# 3x8ButV1_3_6.net
KiCad netlist of a schematic drawn in EAGLE
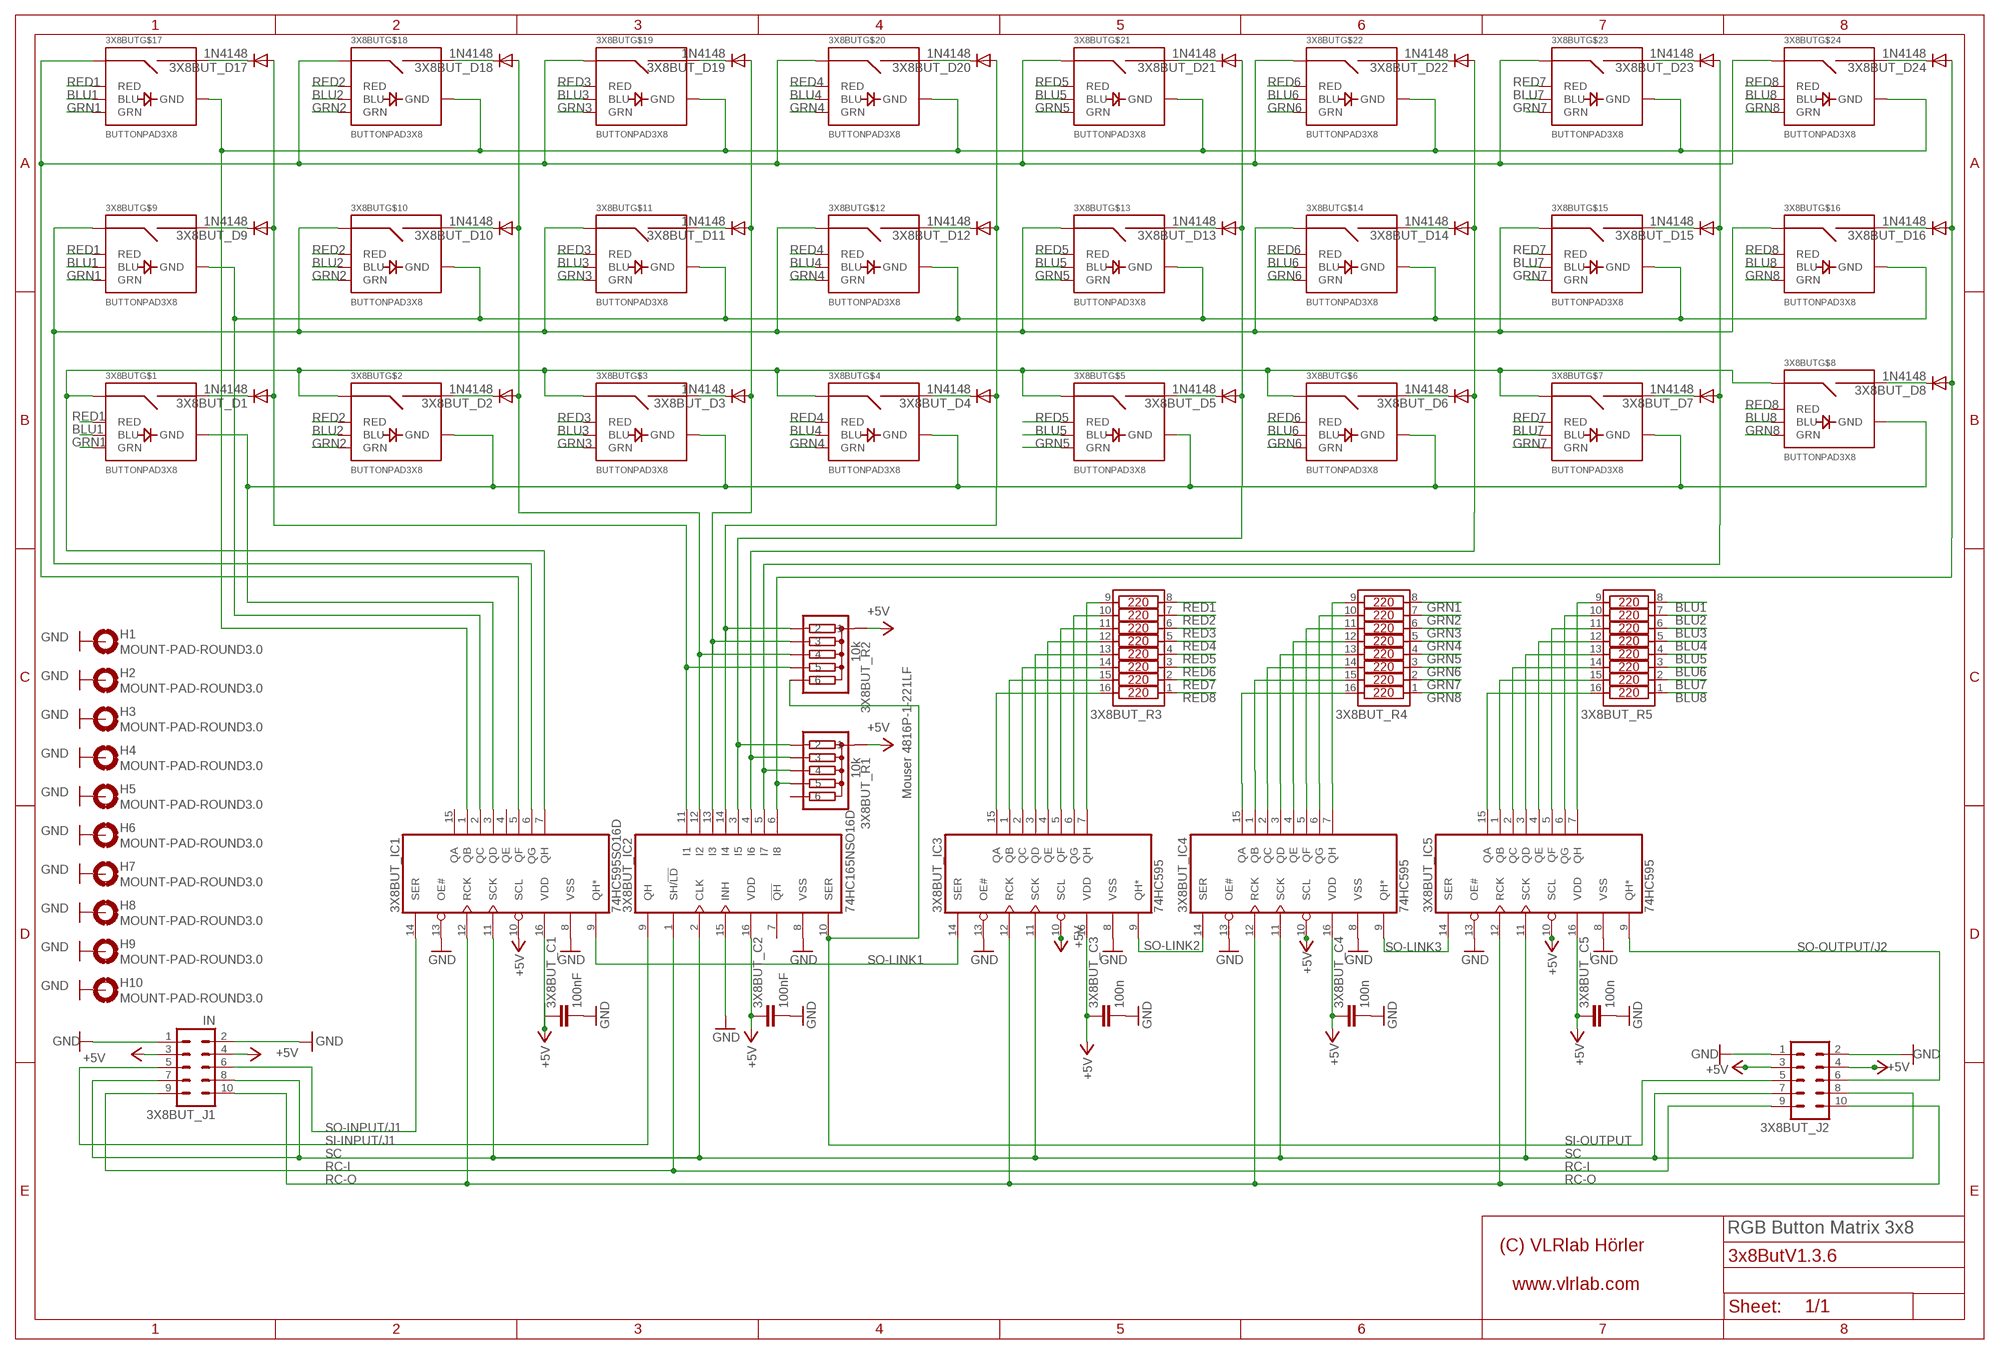
[diagram p0: schematic, sheet 1]

(export (version "E")
  (design (tool "Eeschema 10.0.6"))
  (components
    (comp (ref "3X8BUT")
      (value "BUTTONPAD3X8")
      (footprint "eagle-import:BUTTONPAD3X8")
      (libsource (lib "eagle-import") (part "BUTTONPAD3X8"))
    )
    (comp (ref "3X8BUT_C1")
      (value "100nF")
      (footprint "eagle-import:C025-030X050")
      (libsource (lib "eagle-import") (part "C-EU025-030X050"))
    )
    (comp (ref "3X8BUT_C2")
      (value "100nF")
      (footprint "eagle-import:C025-030X050")
      (libsource (lib "eagle-import") (part "C-EU025-030X050"))
    )
    (comp (ref "3X8BUT_C3")
      (value "100n")
      (footprint "eagle-import:C025-030X050")
      (libsource (lib "eagle-import") (part "C-EU025-030X050"))
    )
    (comp (ref "3X8BUT_C4")
      (value "100n")
      (footprint "eagle-import:C025-030X050")
      (libsource (lib "eagle-import") (part "C-EU025-030X050"))
    )
    (comp (ref "3X8BUT_C5")
      (value "100n")
      (footprint "eagle-import:C025-030X050")
      (libsource (lib "eagle-import") (part "C-EU025-030X050"))
    )
    (comp (ref "3X8BUT_D1")
      (value "1N4148")
      (footprint "eagle-import:DO35-7")
      (libsource (lib "eagle-import") (part "1N4148"))
    )
    (comp (ref "3X8BUT_D2")
      (value "1N4148")
      (footprint "eagle-import:DO35-7")
      (libsource (lib "eagle-import") (part "1N4148"))
    )
    (comp (ref "3X8BUT_D3")
      (value "1N4148")
      (footprint "eagle-import:DO35-7")
      (libsource (lib "eagle-import") (part "1N4148"))
    )
    (comp (ref "3X8BUT_D4")
      (value "1N4148")
      (footprint "eagle-import:DO35-7")
      (libsource (lib "eagle-import") (part "1N4148"))
    )
    (comp (ref "3X8BUT_D5")
      (value "1N4148")
      (footprint "eagle-import:DO35-7")
      (libsource (lib "eagle-import") (part "1N4148"))
    )
    (comp (ref "3X8BUT_D6")
      (value "1N4148")
      (footprint "eagle-import:DO35-7")
      (libsource (lib "eagle-import") (part "1N4148"))
    )
    (comp (ref "3X8BUT_D7")
      (value "1N4148")
      (footprint "eagle-import:DO35-7")
      (libsource (lib "eagle-import") (part "1N4148"))
    )
    (comp (ref "3X8BUT_D8")
      (value "1N4148")
      (footprint "eagle-import:DO35-7")
      (libsource (lib "eagle-import") (part "1N4148"))
    )
    (comp (ref "3X8BUT_D9")
      (value "1N4148")
      (footprint "eagle-import:DO35-7")
      (libsource (lib "eagle-import") (part "1N4148"))
    )
    (comp (ref "3X8BUT_D10")
      (value "1N4148")
      (footprint "eagle-import:DO35-7")
      (libsource (lib "eagle-import") (part "1N4148"))
    )
    (comp (ref "3X8BUT_D11")
      (value "1N4148")
      (footprint "eagle-import:DO35-7")
      (libsource (lib "eagle-import") (part "1N4148"))
    )
    (comp (ref "3X8BUT_D12")
      (value "1N4148")
      (footprint "eagle-import:DO35-7")
      (libsource (lib "eagle-import") (part "1N4148"))
    )
    (comp (ref "3X8BUT_D13")
      (value "1N4148")
      (footprint "eagle-import:DO35-7")
      (libsource (lib "eagle-import") (part "1N4148"))
    )
    (comp (ref "3X8BUT_D14")
      (value "1N4148")
      (footprint "eagle-import:DO35-7")
      (libsource (lib "eagle-import") (part "1N4148"))
    )
    (comp (ref "3X8BUT_D15")
      (value "1N4148")
      (footprint "eagle-import:DO35-7")
      (libsource (lib "eagle-import") (part "1N4148"))
    )
    (comp (ref "3X8BUT_D16")
      (value "1N4148")
      (footprint "eagle-import:DO35-7")
      (libsource (lib "eagle-import") (part "1N4148"))
    )
    (comp (ref "3X8BUT_D17")
      (value "1N4148")
      (footprint "eagle-import:DO35-7")
      (libsource (lib "eagle-import") (part "1N4148"))
    )
    (comp (ref "3X8BUT_D18")
      (value "1N4148")
      (footprint "eagle-import:DO35-7")
      (libsource (lib "eagle-import") (part "1N4148"))
    )
    (comp (ref "3X8BUT_D19")
      (value "1N4148")
      (footprint "eagle-import:DO35-7")
      (libsource (lib "eagle-import") (part "1N4148"))
    )
    (comp (ref "3X8BUT_D20")
      (value "1N4148")
      (footprint "eagle-import:DO35-7")
      (libsource (lib "eagle-import") (part "1N4148"))
    )
    (comp (ref "3X8BUT_D21")
      (value "1N4148")
      (footprint "eagle-import:DO35-7")
      (libsource (lib "eagle-import") (part "1N4148"))
    )
    (comp (ref "3X8BUT_D22")
      (value "1N4148")
      (footprint "eagle-import:DO35-7")
      (libsource (lib "eagle-import") (part "1N4148"))
    )
    (comp (ref "3X8BUT_D23")
      (value "1N4148")
      (footprint "eagle-import:DO35-7")
      (libsource (lib "eagle-import") (part "1N4148"))
    )
    (comp (ref "3X8BUT_D24")
      (value "1N4148")
      (footprint "eagle-import:DO35-7")
      (libsource (lib "eagle-import") (part "1N4148"))
    )
    (comp (ref "3X8BUT_IC1")
      (value "74HC595SO16D")
      (footprint "eagle-import:SO16D")
      (libsource (lib "eagle-import") (part "595-541-165-uln2803_74HC595SO16D"))
    )
    (comp (ref "3X8BUT_IC2")
      (value "74HC165NSO16D")
      (footprint "eagle-import:SO16D")
      (libsource (lib "eagle-import") (part "74HC165NSO16D"))
    )
    (comp (ref "3X8BUT_IC3")
      (value "74HC595")
      (footprint "eagle-import:SO16D")
      (libsource (lib "eagle-import") (part "595-541-165-uln2803_74HC595SO16D"))
    )
    (comp (ref "3X8BUT_IC4")
      (value "74HC595")
      (footprint "eagle-import:SO16D")
      (libsource (lib "eagle-import") (part "595-541-165-uln2803_74HC595SO16D"))
    )
    (comp (ref "3X8BUT_IC5")
      (value "74HC595")
      (footprint "eagle-import:SO16D")
      (libsource (lib "eagle-import") (part "595-541-165-uln2803_74HC595SO16D"))
    )
    (comp (ref "3X8BUT_J1")
      (value "IN")
      (footprint "eagle-import:ML10")
      (libsource (lib "eagle-import") (part "ML10"))
    )
    (comp (ref "3X8BUT_J2")
      (value "ML10")
      (footprint "eagle-import:ML10")
      (libsource (lib "eagle-import") (part "con-ml_ML10"))
    )
    (comp (ref "3X8BUT_R1")
      (value "10k")
      (footprint "eagle-import:SIL6")
      (libsource (lib "eagle-import") (part "4306R"))
    )
    (comp (ref "3X8BUT_R2")
      (value "10k")
      (footprint "eagle-import:SIL6")
      (libsource (lib "eagle-import") (part "4306R"))
    )
    (comp (ref "3X8BUT_R3")
      (value "4816P-1SOIC16W")
      (footprint "eagle-import:SOIC16W")
      (libsource (lib "eagle-import") (part "4816P-1SOIC16W"))
    )
    (comp (ref "3X8BUT_R4")
      (value "4816P-1SOIC16W")
      (footprint "eagle-import:SOIC16W")
      (libsource (lib "eagle-import") (part "4816P-1SOIC16W"))
    )
    (comp (ref "3X8BUT_R5")
      (value "4816P-1SOIC16W")
      (footprint "eagle-import:SOIC16W")
      (libsource (lib "eagle-import") (part "4816P-1SOIC16W"))
    )
    (comp (ref "H1")
      (value "MOUNT-PAD-ROUND3.0")
      (footprint "eagle-import:3,0-PAD")
      (libsource (lib "eagle-import") (part "MOUNT-PAD-ROUND3.0"))
    )
    (comp (ref "H2")
      (value "MOUNT-PAD-ROUND3.0")
      (footprint "eagle-import:3,0-PAD")
      (libsource (lib "eagle-import") (part "MOUNT-PAD-ROUND3.0"))
    )
    (comp (ref "H3")
      (value "MOUNT-PAD-ROUND3.0")
      (footprint "eagle-import:3,0-PAD")
      (libsource (lib "eagle-import") (part "MOUNT-PAD-ROUND3.0"))
    )
    (comp (ref "H4")
      (value "MOUNT-PAD-ROUND3.0")
      (footprint "eagle-import:3,0-PAD")
      (libsource (lib "eagle-import") (part "MOUNT-PAD-ROUND3.0"))
    )
    (comp (ref "H5")
      (value "MOUNT-PAD-ROUND3.0")
      (footprint "eagle-import:3,0-PAD")
      (libsource (lib "eagle-import") (part "MOUNT-PAD-ROUND3.0"))
    )
    (comp (ref "H6")
      (value "MOUNT-PAD-ROUND3.0")
      (footprint "eagle-import:3,0-PAD")
      (libsource (lib "eagle-import") (part "MOUNT-PAD-ROUND3.0"))
    )
    (comp (ref "H7")
      (value "MOUNT-PAD-ROUND3.0")
      (footprint "eagle-import:3,0-PAD")
      (libsource (lib "eagle-import") (part "MOUNT-PAD-ROUND3.0"))
    )
    (comp (ref "H8")
      (value "MOUNT-PAD-ROUND3.0")
      (footprint "eagle-import:3,0-PAD")
      (libsource (lib "eagle-import") (part "MOUNT-PAD-ROUND3.0"))
    )
    (comp (ref "H9")
      (value "MOUNT-PAD-ROUND3.0")
      (footprint "eagle-import:3,0-PAD")
      (libsource (lib "eagle-import") (part "MOUNT-PAD-ROUND3.0"))
    )
    (comp (ref "H10")
      (value "MOUNT-PAD-ROUND3.0")
      (footprint "eagle-import:3,0-PAD")
      (libsource (lib "eagle-import") (part "MOUNT-PAD-ROUND3.0"))
    )
  )
  (nets
    (net (code "1") (name "+5V") (class "Default")
      (node (ref "3X8BUT_C1") (pin "1") (pinfunction "1_1") (pintype "passive"))
      (node (ref "3X8BUT_C2") (pin "1") (pinfunction "1_1") (pintype "passive"))
      (node (ref "3X8BUT_C3") (pin "1") (pinfunction "1_1") (pintype "passive"))
      (node (ref "3X8BUT_C4") (pin "1") (pinfunction "1_1") (pintype "passive"))
      (node (ref "3X8BUT_C5") (pin "1") (pinfunction "1_1") (pintype "passive"))
      (node (ref "3X8BUT_IC1") (pin "10") (pinfunction "SCL_10") (pintype "input"))
      (node (ref "3X8BUT_IC1") (pin "16") (pinfunction "VDD_16") (pintype "power_in"))
      (node (ref "3X8BUT_IC2") (pin "16") (pinfunction "VDD_16") (pintype "power_in"))
      (node (ref "3X8BUT_IC3") (pin "10") (pinfunction "SCL_10") (pintype "input"))
      (node (ref "3X8BUT_IC3") (pin "16") (pinfunction "VDD_16") (pintype "power_in"))
      (node (ref "3X8BUT_IC4") (pin "10") (pinfunction "SCL_10") (pintype "input"))
      (node (ref "3X8BUT_IC4") (pin "16") (pinfunction "VDD_16") (pintype "power_in"))
      (node (ref "3X8BUT_IC5") (pin "10") (pinfunction "SCL_10") (pintype "input"))
      (node (ref "3X8BUT_IC5") (pin "16") (pinfunction "VDD_16") (pintype "power_in"))
      (node (ref "3X8BUT_J1") (pin "3") (pinfunction "3_3") (pintype "passive"))
      (node (ref "3X8BUT_J1") (pin "4") (pinfunction "4_4") (pintype "passive"))
      (node (ref "3X8BUT_J2") (pin "3") (pinfunction "3_3") (pintype "passive"))
      (node (ref "3X8BUT_J2") (pin "4") (pinfunction "4_4") (pintype "passive"))
      (node (ref "3X8BUT_R1") (pin "1") (pinfunction "1_1") (pintype "passive"))
      (node (ref "3X8BUT_R2") (pin "1") (pinfunction "1_1") (pintype "passive"))
    )
    (net (code "2") (name "/BLU1") (class "Default")
      (node (ref "3X8BUT") (pin "BLU1") (pinfunction "BLU_BLU1") (pintype "bidirectional"))
      (node (ref "3X8BUT") (pin "BLU17") (pinfunction "BLU_BLU17") (pintype "bidirectional"))
      (node (ref "3X8BUT") (pin "BLU9") (pinfunction "BLU_BLU9") (pintype "bidirectional"))
      (node (ref "3X8BUT_R5") (pin "8") (pinfunction "P$8_8") (pintype "passive"))
    )
    (net (code "3") (name "/BLU2") (class "Default")
      (node (ref "3X8BUT") (pin "BLU10") (pinfunction "BLU_BLU10") (pintype "bidirectional"))
      (node (ref "3X8BUT") (pin "BLU18") (pinfunction "BLU_BLU18") (pintype "bidirectional"))
      (node (ref "3X8BUT") (pin "BLU2") (pinfunction "BLU_BLU2") (pintype "bidirectional"))
      (node (ref "3X8BUT_R5") (pin "7") (pinfunction "P$7_7") (pintype "passive"))
    )
    (net (code "4") (name "/BLU3") (class "Default")
      (node (ref "3X8BUT") (pin "BLU11") (pinfunction "BLU_BLU11") (pintype "bidirectional"))
      (node (ref "3X8BUT") (pin "BLU19") (pinfunction "BLU_BLU19") (pintype "bidirectional"))
      (node (ref "3X8BUT") (pin "BLU3") (pinfunction "BLU_BLU3") (pintype "bidirectional"))
      (node (ref "3X8BUT_R5") (pin "6") (pinfunction "P$6_6") (pintype "passive"))
    )
    (net (code "5") (name "/BLU4") (class "Default")
      (node (ref "3X8BUT") (pin "BLU12") (pinfunction "BLU_BLU12") (pintype "bidirectional"))
      (node (ref "3X8BUT") (pin "BLU20") (pinfunction "BLU_BLU20") (pintype "bidirectional"))
      (node (ref "3X8BUT") (pin "BLU4") (pinfunction "BLU_BLU4") (pintype "bidirectional"))
      (node (ref "3X8BUT_R5") (pin "5") (pinfunction "P$5_5") (pintype "passive"))
    )
    (net (code "6") (name "/BLU5") (class "Default")
      (node (ref "3X8BUT") (pin "BLU13") (pinfunction "BLU_BLU13") (pintype "bidirectional"))
      (node (ref "3X8BUT") (pin "BLU21") (pinfunction "BLU_BLU21") (pintype "bidirectional"))
      (node (ref "3X8BUT") (pin "BLU5") (pinfunction "BLU_BLU5") (pintype "bidirectional"))
      (node (ref "3X8BUT_R5") (pin "4") (pinfunction "P$4_4") (pintype "passive"))
    )
    (net (code "7") (name "/BLU6") (class "Default")
      (node (ref "3X8BUT") (pin "BLU14") (pinfunction "BLU_BLU14") (pintype "bidirectional"))
      (node (ref "3X8BUT") (pin "BLU22") (pinfunction "BLU_BLU22") (pintype "bidirectional"))
      (node (ref "3X8BUT") (pin "BLU6") (pinfunction "BLU_BLU6") (pintype "bidirectional"))
      (node (ref "3X8BUT_R5") (pin "3") (pinfunction "P$3_3") (pintype "passive"))
    )
    (net (code "8") (name "/BLU7") (class "Default")
      (node (ref "3X8BUT") (pin "BLU15") (pinfunction "BLU_BLU15") (pintype "bidirectional"))
      (node (ref "3X8BUT") (pin "BLU23") (pinfunction "BLU_BLU23") (pintype "bidirectional"))
      (node (ref "3X8BUT") (pin "BLU7") (pinfunction "BLU_BLU7") (pintype "bidirectional"))
      (node (ref "3X8BUT_R5") (pin "2") (pinfunction "P$2_2") (pintype "passive"))
    )
    (net (code "9") (name "/BLU8") (class "Default")
      (node (ref "3X8BUT") (pin "BLU16") (pinfunction "BLU_BLU16") (pintype "bidirectional"))
      (node (ref "3X8BUT") (pin "BLU24") (pinfunction "BLU_BLU24") (pintype "bidirectional"))
      (node (ref "3X8BUT") (pin "BLU8") (pinfunction "BLU_BLU8") (pintype "bidirectional"))
      (node (ref "3X8BUT_R5") (pin "1") (pinfunction "P$1_1") (pintype "passive"))
    )
    (net (code "10") (name "/GRN1") (class "Default")
      (node (ref "3X8BUT") (pin "GRN1") (pinfunction "GRN_GRN1") (pintype "bidirectional"))
      (node (ref "3X8BUT") (pin "GRN17") (pinfunction "GRN_GRN17") (pintype "bidirectional"))
      (node (ref "3X8BUT") (pin "GRN9") (pinfunction "GRN_GRN9") (pintype "bidirectional"))
      (node (ref "3X8BUT_R4") (pin "8") (pinfunction "P$8_8") (pintype "passive"))
    )
    (net (code "11") (name "/GRN2") (class "Default")
      (node (ref "3X8BUT") (pin "GRN10") (pinfunction "GRN_GRN10") (pintype "bidirectional"))
      (node (ref "3X8BUT") (pin "GRN18") (pinfunction "GRN_GRN18") (pintype "bidirectional"))
      (node (ref "3X8BUT") (pin "GRN2") (pinfunction "GRN_GRN2") (pintype "bidirectional"))
      (node (ref "3X8BUT_R4") (pin "7") (pinfunction "P$7_7") (pintype "passive"))
    )
    (net (code "12") (name "/GRN3") (class "Default")
      (node (ref "3X8BUT") (pin "GRN11") (pinfunction "GRN_GRN11") (pintype "bidirectional"))
      (node (ref "3X8BUT") (pin "GRN19") (pinfunction "GRN_GRN19") (pintype "bidirectional"))
      (node (ref "3X8BUT") (pin "GRN3") (pinfunction "GRN_GRN3") (pintype "bidirectional"))
      (node (ref "3X8BUT_R4") (pin "6") (pinfunction "P$6_6") (pintype "passive"))
    )
    (net (code "13") (name "/GRN4") (class "Default")
      (node (ref "3X8BUT") (pin "GRN12") (pinfunction "GRN_GRN12") (pintype "bidirectional"))
      (node (ref "3X8BUT") (pin "GRN20") (pinfunction "GRN_GRN20") (pintype "bidirectional"))
      (node (ref "3X8BUT") (pin "GRN4") (pinfunction "GRN_GRN4") (pintype "bidirectional"))
      (node (ref "3X8BUT_R4") (pin "5") (pinfunction "P$5_5") (pintype "passive"))
    )
    (net (code "14") (name "/GRN5") (class "Default")
      (node (ref "3X8BUT") (pin "GRN13") (pinfunction "GRN_GRN13") (pintype "bidirectional"))
      (node (ref "3X8BUT") (pin "GRN21") (pinfunction "GRN_GRN21") (pintype "bidirectional"))
      (node (ref "3X8BUT") (pin "GRN5") (pinfunction "GRN_GRN5") (pintype "bidirectional"))
      (node (ref "3X8BUT_R4") (pin "4") (pinfunction "P$4_4") (pintype "passive"))
    )
    (net (code "15") (name "/GRN6") (class "Default")
      (node (ref "3X8BUT") (pin "GRN14") (pinfunction "GRN_GRN14") (pintype "bidirectional"))
      (node (ref "3X8BUT") (pin "GRN22") (pinfunction "GRN_GRN22") (pintype "bidirectional"))
      (node (ref "3X8BUT") (pin "GRN6") (pinfunction "GRN_GRN6") (pintype "bidirectional"))
      (node (ref "3X8BUT_R4") (pin "3") (pinfunction "P$3_3") (pintype "passive"))
    )
    (net (code "16") (name "/GRN7") (class "Default")
      (node (ref "3X8BUT") (pin "GRN15") (pinfunction "GRN_GRN15") (pintype "bidirectional"))
      (node (ref "3X8BUT") (pin "GRN23") (pinfunction "GRN_GRN23") (pintype "bidirectional"))
      (node (ref "3X8BUT") (pin "GRN7") (pinfunction "GRN_GRN7") (pintype "bidirectional"))
      (node (ref "3X8BUT_R4") (pin "2") (pinfunction "P$2_2") (pintype "passive"))
    )
    (net (code "17") (name "/GRN8") (class "Default")
      (node (ref "3X8BUT") (pin "GRN16") (pinfunction "GRN_GRN16") (pintype "bidirectional"))
      (node (ref "3X8BUT") (pin "GRN24") (pinfunction "GRN_GRN24") (pintype "bidirectional"))
      (node (ref "3X8BUT") (pin "GRN8") (pinfunction "GRN_GRN8") (pintype "bidirectional"))
      (node (ref "3X8BUT_R4") (pin "1") (pinfunction "P$1_1") (pintype "passive"))
    )
    (net (code "18") (name "/RC-I") (class "Default")
      (node (ref "3X8BUT_IC2") (pin "1") (pinfunction "SH/~{LD}_1") (pintype "input"))
      (node (ref "3X8BUT_J1") (pin "9") (pinfunction "9_9") (pintype "passive"))
      (node (ref "3X8BUT_J2") (pin "9") (pinfunction "9_9") (pintype "passive"))
    )
    (net (code "19") (name "/RC-O") (class "Default")
      (node (ref "3X8BUT_IC1") (pin "12") (pinfunction "RCK_12") (pintype "input"))
      (node (ref "3X8BUT_IC3") (pin "12") (pinfunction "RCK_12") (pintype "input"))
      (node (ref "3X8BUT_IC4") (pin "12") (pinfunction "RCK_12") (pintype "input"))
      (node (ref "3X8BUT_IC5") (pin "12") (pinfunction "RCK_12") (pintype "input"))
      (node (ref "3X8BUT_J1") (pin "10") (pinfunction "10_10") (pintype "passive"))
      (node (ref "3X8BUT_J2") (pin "10") (pinfunction "10_10") (pintype "passive"))
    )
    (net (code "20") (name "/RED1") (class "Default")
      (node (ref "3X8BUT") (pin "RED1") (pinfunction "RED_RED1") (pintype "bidirectional"))
      (node (ref "3X8BUT") (pin "RED17") (pinfunction "RED_RED17") (pintype "bidirectional"))
      (node (ref "3X8BUT") (pin "RED9") (pinfunction "RED_RED9") (pintype "bidirectional"))
      (node (ref "3X8BUT_R3") (pin "8") (pinfunction "P$8_8") (pintype "passive"))
    )
    (net (code "21") (name "/RED2") (class "Default")
      (node (ref "3X8BUT") (pin "RED10") (pinfunction "RED_RED10") (pintype "bidirectional"))
      (node (ref "3X8BUT") (pin "RED18") (pinfunction "RED_RED18") (pintype "bidirectional"))
      (node (ref "3X8BUT") (pin "RED2") (pinfunction "RED_RED2") (pintype "bidirectional"))
      (node (ref "3X8BUT_R3") (pin "7") (pinfunction "P$7_7") (pintype "passive"))
    )
    (net (code "22") (name "/RED3") (class "Default")
      (node (ref "3X8BUT") (pin "RED11") (pinfunction "RED_RED11") (pintype "bidirectional"))
      (node (ref "3X8BUT") (pin "RED19") (pinfunction "RED_RED19") (pintype "bidirectional"))
      (node (ref "3X8BUT") (pin "RED3") (pinfunction "RED_RED3") (pintype "bidirectional"))
      (node (ref "3X8BUT_R3") (pin "6") (pinfunction "P$6_6") (pintype "passive"))
    )
    (net (code "23") (name "/RED4") (class "Default")
      (node (ref "3X8BUT") (pin "RED12") (pinfunction "RED_RED12") (pintype "bidirectional"))
      (node (ref "3X8BUT") (pin "RED20") (pinfunction "RED_RED20") (pintype "bidirectional"))
      (node (ref "3X8BUT") (pin "RED4") (pinfunction "RED_RED4") (pintype "bidirectional"))
      (node (ref "3X8BUT_R3") (pin "5") (pinfunction "P$5_5") (pintype "passive"))
    )
    (net (code "24") (name "/RED5") (class "Default")
      (node (ref "3X8BUT") (pin "RED13") (pinfunction "RED_RED13") (pintype "bidirectional"))
      (node (ref "3X8BUT") (pin "RED21") (pinfunction "RED_RED21") (pintype "bidirectional"))
      (node (ref "3X8BUT") (pin "RED5") (pinfunction "RED_RED5") (pintype "bidirectional"))
      (node (ref "3X8BUT_R3") (pin "4") (pinfunction "P$4_4") (pintype "passive"))
    )
    (net (code "25") (name "/RED6") (class "Default")
      (node (ref "3X8BUT") (pin "RED14") (pinfunction "RED_RED14") (pintype "bidirectional"))
      (node (ref "3X8BUT") (pin "RED22") (pinfunction "RED_RED22") (pintype "bidirectional"))
      (node (ref "3X8BUT") (pin "RED6") (pinfunction "RED_RED6") (pintype "bidirectional"))
      (node (ref "3X8BUT_R3") (pin "3") (pinfunction "P$3_3") (pintype "passive"))
    )
    (net (code "26") (name "/RED7") (class "Default")
      (node (ref "3X8BUT") (pin "RED15") (pinfunction "RED_RED15") (pintype "bidirectional"))
      (node (ref "3X8BUT") (pin "RED23") (pinfunction "RED_RED23") (pintype "bidirectional"))
      (node (ref "3X8BUT") (pin "RED7") (pinfunction "RED_RED7") (pintype "bidirectional"))
      (node (ref "3X8BUT_R3") (pin "2") (pinfunction "P$2_2") (pintype "passive"))
    )
    (net (code "27") (name "/RED8") (class "Default")
      (node (ref "3X8BUT") (pin "RED16") (pinfunction "RED_RED16") (pintype "bidirectional"))
      (node (ref "3X8BUT") (pin "RED24") (pinfunction "RED_RED24") (pintype "bidirectional"))
      (node (ref "3X8BUT") (pin "RED8") (pinfunction "RED_RED8") (pintype "bidirectional"))
      (node (ref "3X8BUT_R3") (pin "1") (pinfunction "P$1_1") (pintype "passive"))
    )
    (net (code "28") (name "/SC") (class "Default")
      (node (ref "3X8BUT_IC1") (pin "11") (pinfunction "SCK_11") (pintype "input"))
      (node (ref "3X8BUT_IC2") (pin "2") (pinfunction "CLK_2") (pintype "input"))
      (node (ref "3X8BUT_IC3") (pin "11") (pinfunction "SCK_11") (pintype "input"))
      (node (ref "3X8BUT_IC4") (pin "11") (pinfunction "SCK_11") (pintype "input"))
      (node (ref "3X8BUT_IC5") (pin "11") (pinfunction "SCK_11") (pintype "input"))
      (node (ref "3X8BUT_J1") (pin "7") (pinfunction "7_7") (pintype "passive"))
      (node (ref "3X8BUT_J1") (pin "8") (pinfunction "8_8") (pintype "passive"))
      (node (ref "3X8BUT_J2") (pin "7") (pinfunction "7_7") (pintype "passive"))
      (node (ref "3X8BUT_J2") (pin "8") (pinfunction "8_8") (pintype "passive"))
    )
    (net (code "29") (name "/SI-INPUT{slash}J1") (class "Default")
      (node (ref "3X8BUT_IC2") (pin "9") (pinfunction "QH_9") (pintype "output"))
      (node (ref "3X8BUT_J1") (pin "5") (pinfunction "5_5") (pintype "passive"))
    )
    (net (code "30") (name "/SI-OUTPUT") (class "Default")
      (node (ref "3X8BUT_IC2") (pin "10") (pinfunction "SER_10") (pintype "input"))
      (node (ref "3X8BUT_J2") (pin "5") (pinfunction "5_5") (pintype "passive"))
      (node (ref "3X8BUT_R2") (pin "6") (pinfunction "6_6") (pintype "passive"))
    )
    (net (code "31") (name "/SO-INPUT{slash}J1") (class "Default")
      (node (ref "3X8BUT_IC1") (pin "14") (pinfunction "SER_14") (pintype "input"))
      (node (ref "3X8BUT_J1") (pin "6") (pinfunction "6_6") (pintype "passive"))
    )
    (net (code "32") (name "/SO-LINK1") (class "Default")
      (node (ref "3X8BUT_IC1") (pin "9") (pinfunction "QH*_9") (pintype "tri_state"))
      (node (ref "3X8BUT_IC3") (pin "14") (pinfunction "SER_14") (pintype "input"))
    )
    (net (code "33") (name "/SO-LINK2") (class "Default")
      (node (ref "3X8BUT_IC3") (pin "9") (pinfunction "QH*_9") (pintype "tri_state"))
      (node (ref "3X8BUT_IC4") (pin "14") (pinfunction "SER_14") (pintype "input"))
    )
    (net (code "34") (name "/SO-LINK3") (class "Default")
      (node (ref "3X8BUT_IC4") (pin "9") (pinfunction "QH*_9") (pintype "tri_state"))
      (node (ref "3X8BUT_IC5") (pin "14") (pinfunction "SER_14") (pintype "input"))
    )
    (net (code "35") (name "/SO-OUTPUT{slash}J2") (class "Default")
      (node (ref "3X8BUT_IC5") (pin "9") (pinfunction "QH*_9") (pintype "tri_state"))
      (node (ref "3X8BUT_J2") (pin "6") (pinfunction "6_6") (pintype "passive"))
    )
    (net (code "36") (name "GND") (class "Default")
      (node (ref "3X8BUT_C1") (pin "2") (pinfunction "2_2") (pintype "passive"))
      (node (ref "3X8BUT_C2") (pin "2") (pinfunction "2_2") (pintype "passive"))
      (node (ref "3X8BUT_C3") (pin "2") (pinfunction "2_2") (pintype "passive"))
      (node (ref "3X8BUT_C4") (pin "2") (pinfunction "2_2") (pintype "passive"))
      (node (ref "3X8BUT_C5") (pin "2") (pinfunction "2_2") (pintype "passive"))
      (node (ref "3X8BUT_IC1") (pin "13") (pinfunction "OE#_13") (pintype "input"))
      (node (ref "3X8BUT_IC1") (pin "8") (pinfunction "VSS_8") (pintype "power_in"))
      (node (ref "3X8BUT_IC2") (pin "15") (pinfunction "INH_15") (pintype "input"))
      (node (ref "3X8BUT_IC2") (pin "8") (pinfunction "VSS_8") (pintype "power_in"))
      (node (ref "3X8BUT_IC3") (pin "13") (pinfunction "OE#_13") (pintype "input"))
      (node (ref "3X8BUT_IC3") (pin "8") (pinfunction "VSS_8") (pintype "power_in"))
      (node (ref "3X8BUT_IC4") (pin "13") (pinfunction "OE#_13") (pintype "input"))
      (node (ref "3X8BUT_IC4") (pin "8") (pinfunction "VSS_8") (pintype "power_in"))
      (node (ref "3X8BUT_IC5") (pin "13") (pinfunction "OE#_13") (pintype "input"))
      (node (ref "3X8BUT_IC5") (pin "8") (pinfunction "VSS_8") (pintype "power_in"))
      (node (ref "3X8BUT_J1") (pin "1") (pinfunction "1_1") (pintype "passive"))
      (node (ref "3X8BUT_J1") (pin "2") (pinfunction "2_2") (pintype "passive"))
      (node (ref "3X8BUT_J2") (pin "1") (pinfunction "1_1") (pintype "passive"))
      (node (ref "3X8BUT_J2") (pin "2") (pinfunction "2_2") (pintype "passive"))
      (node (ref "H1") (pin "B3,0") (pinfunction "MOUNT_B3,0") (pintype "passive"))
      (node (ref "H10") (pin "B3,0") (pinfunction "MOUNT_B3,0") (pintype "passive"))
      (node (ref "H2") (pin "B3,0") (pinfunction "MOUNT_B3,0") (pintype "passive"))
      (node (ref "H3") (pin "B3,0") (pinfunction "MOUNT_B3,0") (pintype "passive"))
      (node (ref "H4") (pin "B3,0") (pinfunction "MOUNT_B3,0") (pintype "passive"))
      (node (ref "H5") (pin "B3,0") (pinfunction "MOUNT_B3,0") (pintype "passive"))
      (node (ref "H6") (pin "B3,0") (pinfunction "MOUNT_B3,0") (pintype "passive"))
      (node (ref "H7") (pin "B3,0") (pinfunction "MOUNT_B3,0") (pintype "passive"))
      (node (ref "H8") (pin "B3,0") (pinfunction "MOUNT_B3,0") (pintype "passive"))
      (node (ref "H9") (pin "B3,0") (pinfunction "MOUNT_B3,0") (pintype "passive"))
    )
    (net (code "37") (name "Net-(3X8BUTA-GND)") (class "Default")
      (node (ref "3X8BUT") (pin "GND1") (pinfunction "GND_GND1") (pintype "bidirectional"))
      (node (ref "3X8BUT") (pin "GND2") (pinfunction "GND_GND2") (pintype "bidirectional"))
      (node (ref "3X8BUT") (pin "GND3") (pinfunction "GND_GND3") (pintype "bidirectional"))
      (node (ref "3X8BUT") (pin "GND4") (pinfunction "GND_GND4") (pintype "bidirectional"))
      (node (ref "3X8BUT") (pin "GND5") (pinfunction "GND_GND5") (pintype "bidirectional"))
      (node (ref "3X8BUT") (pin "GND6") (pinfunction "GND_GND6") (pintype "bidirectional"))
      (node (ref "3X8BUT") (pin "GND7") (pinfunction "GND_GND7") (pintype "bidirectional"))
      (node (ref "3X8BUT") (pin "GND8") (pinfunction "GND_GND8") (pintype "bidirectional"))
      (node (ref "3X8BUT_IC1") (pin "3") (pinfunction "QD_3") (pintype "tri_state"))
    )
    (net (code "38") (name "Net-(3X8BUTA-SIG1)") (class "Default")
      (node (ref "3X8BUT") (pin "SIG01") (pinfunction "SIG1_SIG01") (pintype "bidirectional"))
      (node (ref "3X8BUT") (pin "SIG03") (pinfunction "SIG1_SIG03") (pintype "bidirectional"))
      (node (ref "3X8BUT") (pin "SIG05") (pinfunction "SIG1_SIG05") (pintype "bidirectional"))
      (node (ref "3X8BUT") (pin "SIG07") (pinfunction "SIG1_SIG07") (pintype "bidirectional"))
      (node (ref "3X8BUT") (pin "SIG09") (pinfunction "SIG1_SIG09") (pintype "bidirectional"))
      (node (ref "3X8BUT") (pin "SIG11") (pinfunction "SIG1_SIG11") (pintype "bidirectional"))
      (node (ref "3X8BUT") (pin "SIG13") (pinfunction "SIG1_SIG13") (pintype "bidirectional"))
      (node (ref "3X8BUT") (pin "SIG15") (pinfunction "SIG1_SIG15") (pintype "bidirectional"))
      (node (ref "3X8BUT_IC1") (pin "7") (pinfunction "QH_7") (pintype "tri_state"))
    )
    (net (code "39") (name "Net-(3X8BUTA-SIG2)") (class "Default")
      (node (ref "3X8BUT") (pin "SIG02") (pinfunction "SIG2_SIG02") (pintype "bidirectional"))
      (node (ref "3X8BUT_D1") (pin "C") (pinfunction "C_C") (pintype "passive"))
    )
    (net (code "40") (name "Net-(3X8BUTB-GND)") (class "Default")
      (node (ref "3X8BUT") (pin "GND10") (pinfunction "GND_GND10") (pintype "bidirectional"))
      (node (ref "3X8BUT") (pin "GND11") (pinfunction "GND_GND11") (pintype "bidirectional"))
      (node (ref "3X8BUT") (pin "GND12") (pinfunction "GND_GND12") (pintype "bidirectional"))
      (node (ref "3X8BUT") (pin "GND13") (pinfunction "GND_GND13") (pintype "bidirectional"))
      (node (ref "3X8BUT") (pin "GND14") (pinfunction "GND_GND14") (pintype "bidirectional"))
      (node (ref "3X8BUT") (pin "GND15") (pinfunction "GND_GND15") (pintype "bidirectional"))
      (node (ref "3X8BUT") (pin "GND16") (pinfunction "GND_GND16") (pintype "bidirectional"))
      (node (ref "3X8BUT") (pin "GND9") (pinfunction "GND_GND9") (pintype "bidirectional"))
      (node (ref "3X8BUT_IC1") (pin "2") (pinfunction "QC_2") (pintype "tri_state"))
    )
    (net (code "41") (name "Net-(3X8BUTB-SIG1)") (class "Default")
      (node (ref "3X8BUT") (pin "SIG17") (pinfunction "SIG1_SIG17") (pintype "bidirectional"))
      (node (ref "3X8BUT") (pin "SIG19") (pinfunction "SIG1_SIG19") (pintype "bidirectional"))
      (node (ref "3X8BUT") (pin "SIG21") (pinfunction "SIG1_SIG21") (pintype "bidirectional"))
      (node (ref "3X8BUT") (pin "SIG23") (pinfunction "SIG1_SIG23") (pintype "bidirectional"))
      (node (ref "3X8BUT") (pin "SIG25") (pinfunction "SIG1_SIG25") (pintype "bidirectional"))
      (node (ref "3X8BUT") (pin "SIG27") (pinfunction "SIG1_SIG27") (pintype "bidirectional"))
      (node (ref "3X8BUT") (pin "SIG29") (pinfunction "SIG1_SIG29") (pintype "bidirectional"))
      (node (ref "3X8BUT") (pin "SIG31") (pinfunction "SIG1_SIG31") (pintype "bidirectional"))
      (node (ref "3X8BUT_IC1") (pin "6") (pinfunction "QG_6") (pintype "tri_state"))
    )
    (net (code "42") (name "Net-(3X8BUTB-SIG2)") (class "Default")
      (node (ref "3X8BUT") (pin "SIG20") (pinfunction "SIG2_SIG20") (pintype "bidirectional"))
      (node (ref "3X8BUT_D10") (pin "C") (pinfunction "C_C") (pintype "passive"))
    )
    (net (code "43") (name "Net-(3X8BUTC-SIG2)") (class "Default")
      (node (ref "3X8BUT") (pin "SIG22") (pinfunction "SIG2_SIG22") (pintype "bidirectional"))
      (node (ref "3X8BUT_D11") (pin "C") (pinfunction "C_C") (pintype "passive"))
    )
    (net (code "44") (name "Net-(3X8BUTD-SIG2)") (class "Default")
      (node (ref "3X8BUT") (pin "SIG24") (pinfunction "SIG2_SIG24") (pintype "bidirectional"))
      (node (ref "3X8BUT_D12") (pin "C") (pinfunction "C_C") (pintype "passive"))
    )
    (net (code "45") (name "Net-(3X8BUTE-SIG2)") (class "Default")
      (node (ref "3X8BUT") (pin "SIG26") (pinfunction "SIG2_SIG26") (pintype "bidirectional"))
      (node (ref "3X8BUT_D13") (pin "C") (pinfunction "C_C") (pintype "passive"))
    )
    (net (code "46") (name "Net-(3X8BUTF-SIG2)") (class "Default")
      (node (ref "3X8BUT") (pin "SIG28") (pinfunction "SIG2_SIG28") (pintype "bidirectional"))
      (node (ref "3X8BUT_D14") (pin "C") (pinfunction "C_C") (pintype "passive"))
    )
    (net (code "47") (name "Net-(3X8BUTG-SIG2)") (class "Default")
      (node (ref "3X8BUT") (pin "SIG30") (pinfunction "SIG2_SIG30") (pintype "bidirectional"))
      (node (ref "3X8BUT_D15") (pin "C") (pinfunction "C_C") (pintype "passive"))
    )
    (net (code "48") (name "Net-(3X8BUTH-SIG2)") (class "Default")
      (node (ref "3X8BUT") (pin "SIG32") (pinfunction "SIG2_SIG32") (pintype "bidirectional"))
      (node (ref "3X8BUT_D16") (pin "C") (pinfunction "C_C") (pintype "passive"))
    )
    (net (code "49") (name "Net-(3X8BUTI-GND)") (class "Default")
      (node (ref "3X8BUT") (pin "GND17") (pinfunction "GND_GND17") (pintype "bidirectional"))
      (node (ref "3X8BUT") (pin "GND18") (pinfunction "GND_GND18") (pintype "bidirectional"))
      (node (ref "3X8BUT") (pin "GND19") (pinfunction "GND_GND19") (pintype "bidirectional"))
      (node (ref "3X8BUT") (pin "GND20") (pinfunction "GND_GND20") (pintype "bidirectional"))
      (node (ref "3X8BUT") (pin "GND21") (pinfunction "GND_GND21") (pintype "bidirectional"))
      (node (ref "3X8BUT") (pin "GND22") (pinfunction "GND_GND22") (pintype "bidirectional"))
      (node (ref "3X8BUT") (pin "GND23") (pinfunction "GND_GND23") (pintype "bidirectional"))
      (node (ref "3X8BUT") (pin "GND24") (pinfunction "GND_GND24") (pintype "bidirectional"))
      (node (ref "3X8BUT_IC1") (pin "1") (pinfunction "QB_1") (pintype "tri_state"))
    )
    (net (code "50") (name "Net-(3X8BUTI-SIG1)") (class "Default")
      (node (ref "3X8BUT") (pin "SIG33") (pinfunction "SIG1_SIG33") (pintype "bidirectional"))
      (node (ref "3X8BUT") (pin "SIG35") (pinfunction "SIG1_SIG35") (pintype "bidirectional"))
      (node (ref "3X8BUT") (pin "SIG37") (pinfunction "SIG1_SIG37") (pintype "bidirectional"))
      (node (ref "3X8BUT") (pin "SIG39") (pinfunction "SIG1_SIG39") (pintype "bidirectional"))
      (node (ref "3X8BUT") (pin "SIG41") (pinfunction "SIG1_SIG41") (pintype "bidirectional"))
      (node (ref "3X8BUT") (pin "SIG43") (pinfunction "SIG1_SIG43") (pintype "bidirectional"))
      (node (ref "3X8BUT") (pin "SIG45") (pinfunction "SIG1_SIG45") (pintype "bidirectional"))
      (node (ref "3X8BUT") (pin "SIG47") (pinfunction "SIG1_SIG47") (pintype "bidirectional"))
      (node (ref "3X8BUT_IC1") (pin "5") (pinfunction "QF_5") (pintype "tri_state"))
    )
    (net (code "51") (name "Net-(3X8BUTI-SIG2)") (class "Default")
      (node (ref "3X8BUT") (pin "SIG34") (pinfunction "SIG2_SIG34") (pintype "bidirectional"))
      (node (ref "3X8BUT_D17") (pin "C") (pinfunction "C_C") (pintype "passive"))
    )
    (net (code "52") (name "Net-(3X8BUTJ-SIG2)") (class "Default")
      (node (ref "3X8BUT") (pin "SIG36") (pinfunction "SIG2_SIG36") (pintype "bidirectional"))
      (node (ref "3X8BUT_D18") (pin "C") (pinfunction "C_C") (pintype "passive"))
    )
    (net (code "53") (name "Net-(3X8BUTK-SIG2)") (class "Default")
      (node (ref "3X8BUT") (pin "SIG38") (pinfunction "SIG2_SIG38") (pintype "bidirectional"))
      (node (ref "3X8BUT_D19") (pin "C") (pinfunction "C_C") (pintype "passive"))
    )
    (net (code "54") (name "Net-(3X8BUTL-SIG2)") (class "Default")
      (node (ref "3X8BUT") (pin "SIG04") (pinfunction "SIG2_SIG04") (pintype "bidirectional"))
      (node (ref "3X8BUT_D2") (pin "C") (pinfunction "C_C") (pintype "passive"))
    )
    (net (code "55") (name "Net-(3X8BUTM-SIG2)") (class "Default")
      (node (ref "3X8BUT") (pin "SIG40") (pinfunction "SIG2_SIG40") (pintype "bidirectional"))
      (node (ref "3X8BUT_D20") (pin "C") (pinfunction "C_C") (pintype "passive"))
    )
    (net (code "56") (name "Net-(3X8BUTN-SIG2)") (class "Default")
      (node (ref "3X8BUT") (pin "SIG42") (pinfunction "SIG2_SIG42") (pintype "bidirectional"))
      (node (ref "3X8BUT_D21") (pin "C") (pinfunction "C_C") (pintype "passive"))
    )
    (net (code "57") (name "Net-(3X8BUTO-SIG2)") (class "Default")
      (node (ref "3X8BUT") (pin "SIG44") (pinfunction "SIG2_SIG44") (pintype "bidirectional"))
      (node (ref "3X8BUT_D22") (pin "C") (pinfunction "C_C") (pintype "passive"))
    )
    (net (code "58") (name "Net-(3X8BUTP-SIG2)") (class "Default")
      (node (ref "3X8BUT") (pin "SIG46") (pinfunction "SIG2_SIG46") (pintype "bidirectional"))
      (node (ref "3X8BUT_D23") (pin "C") (pinfunction "C_C") (pintype "passive"))
    )
    (net (code "59") (name "Net-(3X8BUTQ-SIG2)") (class "Default")
      (node (ref "3X8BUT") (pin "SIG48") (pinfunction "SIG2_SIG48") (pintype "bidirectional"))
      (node (ref "3X8BUT_D24") (pin "C") (pinfunction "C_C") (pintype "passive"))
    )
    (net (code "60") (name "Net-(3X8BUTR-SIG2)") (class "Default")
      (node (ref "3X8BUT") (pin "SIG06") (pinfunction "SIG2_SIG06") (pintype "bidirectional"))
      (node (ref "3X8BUT_D3") (pin "C") (pinfunction "C_C") (pintype "passive"))
    )
    (net (code "61") (name "Net-(3X8BUTS-SIG2)") (class "Default")
      (node (ref "3X8BUT") (pin "SIG08") (pinfunction "SIG2_SIG08") (pintype "bidirectional"))
      (node (ref "3X8BUT_D4") (pin "C") (pinfunction "C_C") (pintype "passive"))
    )
    (net (code "62") (name "Net-(3X8BUTT-SIG2)") (class "Default")
      (node (ref "3X8BUT") (pin "SIG10") (pinfunction "SIG2_SIG10") (pintype "bidirectional"))
      (node (ref "3X8BUT_D5") (pin "C") (pinfunction "C_C") (pintype "passive"))
    )
    (net (code "63") (name "Net-(3X8BUTU-SIG2)") (class "Default")
      (node (ref "3X8BUT") (pin "SIG12") (pinfunction "SIG2_SIG12") (pintype "bidirectional"))
      (node (ref "3X8BUT_D6") (pin "C") (pinfunction "C_C") (pintype "passive"))
    )
    (net (code "64") (name "Net-(3X8BUTV-SIG2)") (class "Default")
      (node (ref "3X8BUT") (pin "SIG14") (pinfunction "SIG2_SIG14") (pintype "bidirectional"))
      (node (ref "3X8BUT_D7") (pin "C") (pinfunction "C_C") (pintype "passive"))
    )
    (net (code "65") (name "Net-(3X8BUTW-SIG2)") (class "Default")
      (node (ref "3X8BUT") (pin "SIG16") (pinfunction "SIG2_SIG16") (pintype "bidirectional"))
      (node (ref "3X8BUT_D8") (pin "C") (pinfunction "C_C") (pintype "passive"))
    )
    (net (code "66") (name "Net-(3X8BUTX-SIG2)") (class "Default")
      (node (ref "3X8BUT") (pin "SIG18") (pinfunction "SIG2_SIG18") (pintype "bidirectional"))
      (node (ref "3X8BUT_D9") (pin "C") (pinfunction "C_C") (pintype "passive"))
    )
    (net (code "67") (name "Net-(3X8BUT_IC2-I1)") (class "Default")
      (node (ref "3X8BUT_D1") (pin "A") (pinfunction "A_A") (pintype "passive"))
      (node (ref "3X8BUT_D17") (pin "A") (pinfunction "A_A") (pintype "passive"))
      (node (ref "3X8BUT_D9") (pin "A") (pinfunction "A_A") (pintype "passive"))
      (node (ref "3X8BUT_IC2") (pin "11") (pinfunction "I1_11") (pintype "input"))
      (node (ref "3X8BUT_R2") (pin "5") (pinfunction "5_5") (pintype "passive"))
    )
    (net (code "68") (name "Net-(3X8BUT_IC2-I2)") (class "Default")
      (node (ref "3X8BUT_D10") (pin "A") (pinfunction "A_A") (pintype "passive"))
      (node (ref "3X8BUT_D18") (pin "A") (pinfunction "A_A") (pintype "passive"))
      (node (ref "3X8BUT_D2") (pin "A") (pinfunction "A_A") (pintype "passive"))
      (node (ref "3X8BUT_IC2") (pin "12") (pinfunction "I2_12") (pintype "input"))
      (node (ref "3X8BUT_R2") (pin "4") (pinfunction "4_4") (pintype "passive"))
    )
    (net (code "69") (name "Net-(3X8BUT_IC2-I3)") (class "Default")
      (node (ref "3X8BUT_D11") (pin "A") (pinfunction "A_A") (pintype "passive"))
      (node (ref "3X8BUT_D19") (pin "A") (pinfunction "A_A") (pintype "passive"))
      (node (ref "3X8BUT_D3") (pin "A") (pinfunction "A_A") (pintype "passive"))
      (node (ref "3X8BUT_IC2") (pin "13") (pinfunction "I3_13") (pintype "input"))
      (node (ref "3X8BUT_R2") (pin "3") (pinfunction "3_3") (pintype "passive"))
    )
    (net (code "70") (name "Net-(3X8BUT_IC2-I4)") (class "Default")
      (node (ref "3X8BUT_D12") (pin "A") (pinfunction "A_A") (pintype "passive"))
      (node (ref "3X8BUT_D20") (pin "A") (pinfunction "A_A") (pintype "passive"))
      (node (ref "3X8BUT_D4") (pin "A") (pinfunction "A_A") (pintype "passive"))
      (node (ref "3X8BUT_IC2") (pin "14") (pinfunction "I4_14") (pintype "input"))
      (node (ref "3X8BUT_R2") (pin "2") (pinfunction "2_2") (pintype "passive"))
    )
    (net (code "71") (name "Net-(3X8BUT_IC2-I5)") (class "Default")
      (node (ref "3X8BUT_D13") (pin "A") (pinfunction "A_A") (pintype "passive"))
      (node (ref "3X8BUT_D21") (pin "A") (pinfunction "A_A") (pintype "passive"))
      (node (ref "3X8BUT_D5") (pin "A") (pinfunction "A_A") (pintype "passive"))
      (node (ref "3X8BUT_IC2") (pin "3") (pinfunction "I5_3") (pintype "input"))
      (node (ref "3X8BUT_R1") (pin "2") (pinfunction "2_2") (pintype "passive"))
    )
    (net (code "72") (name "Net-(3X8BUT_IC2-I6)") (class "Default")
      (node (ref "3X8BUT_D14") (pin "A") (pinfunction "A_A") (pintype "passive"))
      (node (ref "3X8BUT_D22") (pin "A") (pinfunction "A_A") (pintype "passive"))
      (node (ref "3X8BUT_D6") (pin "A") (pinfunction "A_A") (pintype "passive"))
      (node (ref "3X8BUT_IC2") (pin "4") (pinfunction "I6_4") (pintype "input"))
      (node (ref "3X8BUT_R1") (pin "3") (pinfunction "3_3") (pintype "passive"))
    )
    (net (code "73") (name "Net-(3X8BUT_IC2-I7)") (class "Default")
      (node (ref "3X8BUT_D15") (pin "A") (pinfunction "A_A") (pintype "passive"))
      (node (ref "3X8BUT_D23") (pin "A") (pinfunction "A_A") (pintype "passive"))
      (node (ref "3X8BUT_D7") (pin "A") (pinfunction "A_A") (pintype "passive"))
      (node (ref "3X8BUT_IC2") (pin "5") (pinfunction "I7_5") (pintype "input"))
      (node (ref "3X8BUT_R1") (pin "4") (pinfunction "4_4") (pintype "passive"))
    )
    (net (code "74") (name "Net-(3X8BUT_IC2-I8)") (class "Default")
      (node (ref "3X8BUT_D16") (pin "A") (pinfunction "A_A") (pintype "passive"))
      (node (ref "3X8BUT_D24") (pin "A") (pinfunction "A_A") (pintype "passive"))
      (node (ref "3X8BUT_D8") (pin "A") (pinfunction "A_A") (pintype "passive"))
      (node (ref "3X8BUT_IC2") (pin "6") (pinfunction "I8_6") (pintype "input"))
      (node (ref "3X8BUT_R1") (pin "5") (pinfunction "5_5") (pintype "passive"))
    )
    (net (code "75") (name "Net-(3X8BUT_IC3-QA)") (class "Default")
      (node (ref "3X8BUT_IC3") (pin "15") (pinfunction "QA_15") (pintype "tri_state"))
      (node (ref "3X8BUT_R3") (pin "16") (pinfunction "P$16_16") (pintype "passive"))
    )
    (net (code "76") (name "Net-(3X8BUT_IC3-QB)") (class "Default")
      (node (ref "3X8BUT_IC3") (pin "1") (pinfunction "QB_1") (pintype "tri_state"))
      (node (ref "3X8BUT_R3") (pin "15") (pinfunction "P$15_15") (pintype "passive"))
    )
    (net (code "77") (name "Net-(3X8BUT_IC3-QC)") (class "Default")
      (node (ref "3X8BUT_IC3") (pin "2") (pinfunction "QC_2") (pintype "tri_state"))
      (node (ref "3X8BUT_R3") (pin "14") (pinfunction "P$14_14") (pintype "passive"))
    )
    (net (code "78") (name "Net-(3X8BUT_IC3-QD)") (class "Default")
      (node (ref "3X8BUT_IC3") (pin "3") (pinfunction "QD_3") (pintype "tri_state"))
      (node (ref "3X8BUT_R3") (pin "13") (pinfunction "P$13_13") (pintype "passive"))
    )
    (net (code "79") (name "Net-(3X8BUT_IC3-QE)") (class "Default")
      (node (ref "3X8BUT_IC3") (pin "4") (pinfunction "QE_4") (pintype "tri_state"))
      (node (ref "3X8BUT_R3") (pin "12") (pinfunction "P$12_12") (pintype "passive"))
    )
    (net (code "80") (name "Net-(3X8BUT_IC3-QF)") (class "Default")
      (node (ref "3X8BUT_IC3") (pin "5") (pinfunction "QF_5") (pintype "tri_state"))
      (node (ref "3X8BUT_R3") (pin "11") (pinfunction "P$11_11") (pintype "passive"))
    )
    (net (code "81") (name "Net-(3X8BUT_IC3-QG)") (class "Default")
      (node (ref "3X8BUT_IC3") (pin "6") (pinfunction "QG_6") (pintype "tri_state"))
      (node (ref "3X8BUT_R3") (pin "10") (pinfunction "P$10_10") (pintype "passive"))
    )
    (net (code "82") (name "Net-(3X8BUT_IC3-QH)") (class "Default")
      (node (ref "3X8BUT_IC3") (pin "7") (pinfunction "QH_7") (pintype "tri_state"))
      (node (ref "3X8BUT_R3") (pin "9") (pinfunction "P$9_9") (pintype "passive"))
    )
    (net (code "83") (name "Net-(3X8BUT_IC4-QA)") (class "Default")
      (node (ref "3X8BUT_IC4") (pin "15") (pinfunction "QA_15") (pintype "tri_state"))
      (node (ref "3X8BUT_R4") (pin "16") (pinfunction "P$16_16") (pintype "passive"))
    )
    (net (code "84") (name "Net-(3X8BUT_IC4-QB)") (class "Default")
      (node (ref "3X8BUT_IC4") (pin "1") (pinfunction "QB_1") (pintype "tri_state"))
      (node (ref "3X8BUT_R4") (pin "15") (pinfunction "P$15_15") (pintype "passive"))
    )
    (net (code "85") (name "Net-(3X8BUT_IC4-QC)") (class "Default")
      (node (ref "3X8BUT_IC4") (pin "2") (pinfunction "QC_2") (pintype "tri_state"))
      (node (ref "3X8BUT_R4") (pin "14") (pinfunction "P$14_14") (pintype "passive"))
    )
    (net (code "86") (name "Net-(3X8BUT_IC4-QD)") (class "Default")
      (node (ref "3X8BUT_IC4") (pin "3") (pinfunction "QD_3") (pintype "tri_state"))
      (node (ref "3X8BUT_R4") (pin "13") (pinfunction "P$13_13") (pintype "passive"))
    )
    (net (code "87") (name "Net-(3X8BUT_IC4-QE)") (class "Default")
      (node (ref "3X8BUT_IC4") (pin "4") (pinfunction "QE_4") (pintype "tri_state"))
      (node (ref "3X8BUT_R4") (pin "12") (pinfunction "P$12_12") (pintype "passive"))
    )
    (net (code "88") (name "Net-(3X8BUT_IC4-QF)") (class "Default")
      (node (ref "3X8BUT_IC4") (pin "5") (pinfunction "QF_5") (pintype "tri_state"))
      (node (ref "3X8BUT_R4") (pin "11") (pinfunction "P$11_11") (pintype "passive"))
    )
    (net (code "89") (name "Net-(3X8BUT_IC4-QG)") (class "Default")
      (node (ref "3X8BUT_IC4") (pin "6") (pinfunction "QG_6") (pintype "tri_state"))
      (node (ref "3X8BUT_R4") (pin "10") (pinfunction "P$10_10") (pintype "passive"))
    )
    (net (code "90") (name "Net-(3X8BUT_IC4-QH)") (class "Default")
      (node (ref "3X8BUT_IC4") (pin "7") (pinfunction "QH_7") (pintype "tri_state"))
      (node (ref "3X8BUT_R4") (pin "9") (pinfunction "P$9_9") (pintype "passive"))
    )
    (net (code "91") (name "Net-(3X8BUT_IC5-QA)") (class "Default")
      (node (ref "3X8BUT_IC5") (pin "15") (pinfunction "QA_15") (pintype "tri_state"))
      (node (ref "3X8BUT_R5") (pin "16") (pinfunction "P$16_16") (pintype "passive"))
    )
    (net (code "92") (name "Net-(3X8BUT_IC5-QB)") (class "Default")
      (node (ref "3X8BUT_IC5") (pin "1") (pinfunction "QB_1") (pintype "tri_state"))
      (node (ref "3X8BUT_R5") (pin "15") (pinfunction "P$15_15") (pintype "passive"))
    )
    (net (code "93") (name "Net-(3X8BUT_IC5-QC)") (class "Default")
      (node (ref "3X8BUT_IC5") (pin "2") (pinfunction "QC_2") (pintype "tri_state"))
      (node (ref "3X8BUT_R5") (pin "14") (pinfunction "P$14_14") (pintype "passive"))
    )
    (net (code "94") (name "Net-(3X8BUT_IC5-QD)") (class "Default")
      (node (ref "3X8BUT_IC5") (pin "3") (pinfunction "QD_3") (pintype "tri_state"))
      (node (ref "3X8BUT_R5") (pin "13") (pinfunction "P$13_13") (pintype "passive"))
    )
    (net (code "95") (name "Net-(3X8BUT_IC5-QE)") (class "Default")
      (node (ref "3X8BUT_IC5") (pin "4") (pinfunction "QE_4") (pintype "tri_state"))
      (node (ref "3X8BUT_R5") (pin "12") (pinfunction "P$12_12") (pintype "passive"))
    )
    (net (code "96") (name "Net-(3X8BUT_IC5-QF)") (class "Default")
      (node (ref "3X8BUT_IC5") (pin "5") (pinfunction "QF_5") (pintype "tri_state"))
      (node (ref "3X8BUT_R5") (pin "11") (pinfunction "P$11_11") (pintype "passive"))
    )
    (net (code "97") (name "Net-(3X8BUT_IC5-QG)") (class "Default")
      (node (ref "3X8BUT_IC5") (pin "6") (pinfunction "QG_6") (pintype "tri_state"))
      (node (ref "3X8BUT_R5") (pin "10") (pinfunction "P$10_10") (pintype "passive"))
    )
    (net (code "98") (name "Net-(3X8BUT_IC5-QH)") (class "Default")
      (node (ref "3X8BUT_IC5") (pin "7") (pinfunction "QH_7") (pintype "tri_state"))
      (node (ref "3X8BUT_R5") (pin "9") (pinfunction "P$9_9") (pintype "passive"))
    )
    (net (code "99") (name "unconnected-(3X8BUT_IC1-QA-Pad15)") (class "Default")
      (node (ref "3X8BUT_IC1") (pin "15") (pinfunction "QA_15") (pintype "tri_state"))
    )
    (net (code "100") (name "unconnected-(3X8BUT_IC1-QE-Pad4)") (class "Default")
      (node (ref "3X8BUT_IC1") (pin "4") (pinfunction "QE_4") (pintype "tri_state"))
    )
    (net (code "101") (name "unconnected-(3X8BUT_IC2-~{QH}-Pad7)") (class "Default")
      (node (ref "3X8BUT_IC2") (pin "7") (pinfunction "~{QH}_7") (pintype "output"))
    )
    (net (code "102") (name "unconnected-(3X8BUT_R1-Pad6)") (class "Default")
      (node (ref "3X8BUT_R1") (pin "6") (pinfunction "6_6") (pintype "passive"))
    )
  )
)
